# quadcopter.net
KiCad netlist of a schematic drawn in EAGLE
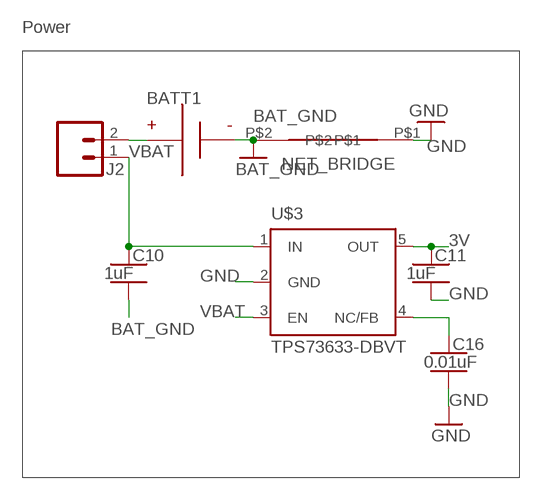
[diagram p0: schematic, sheet 1, part 1 of 2]
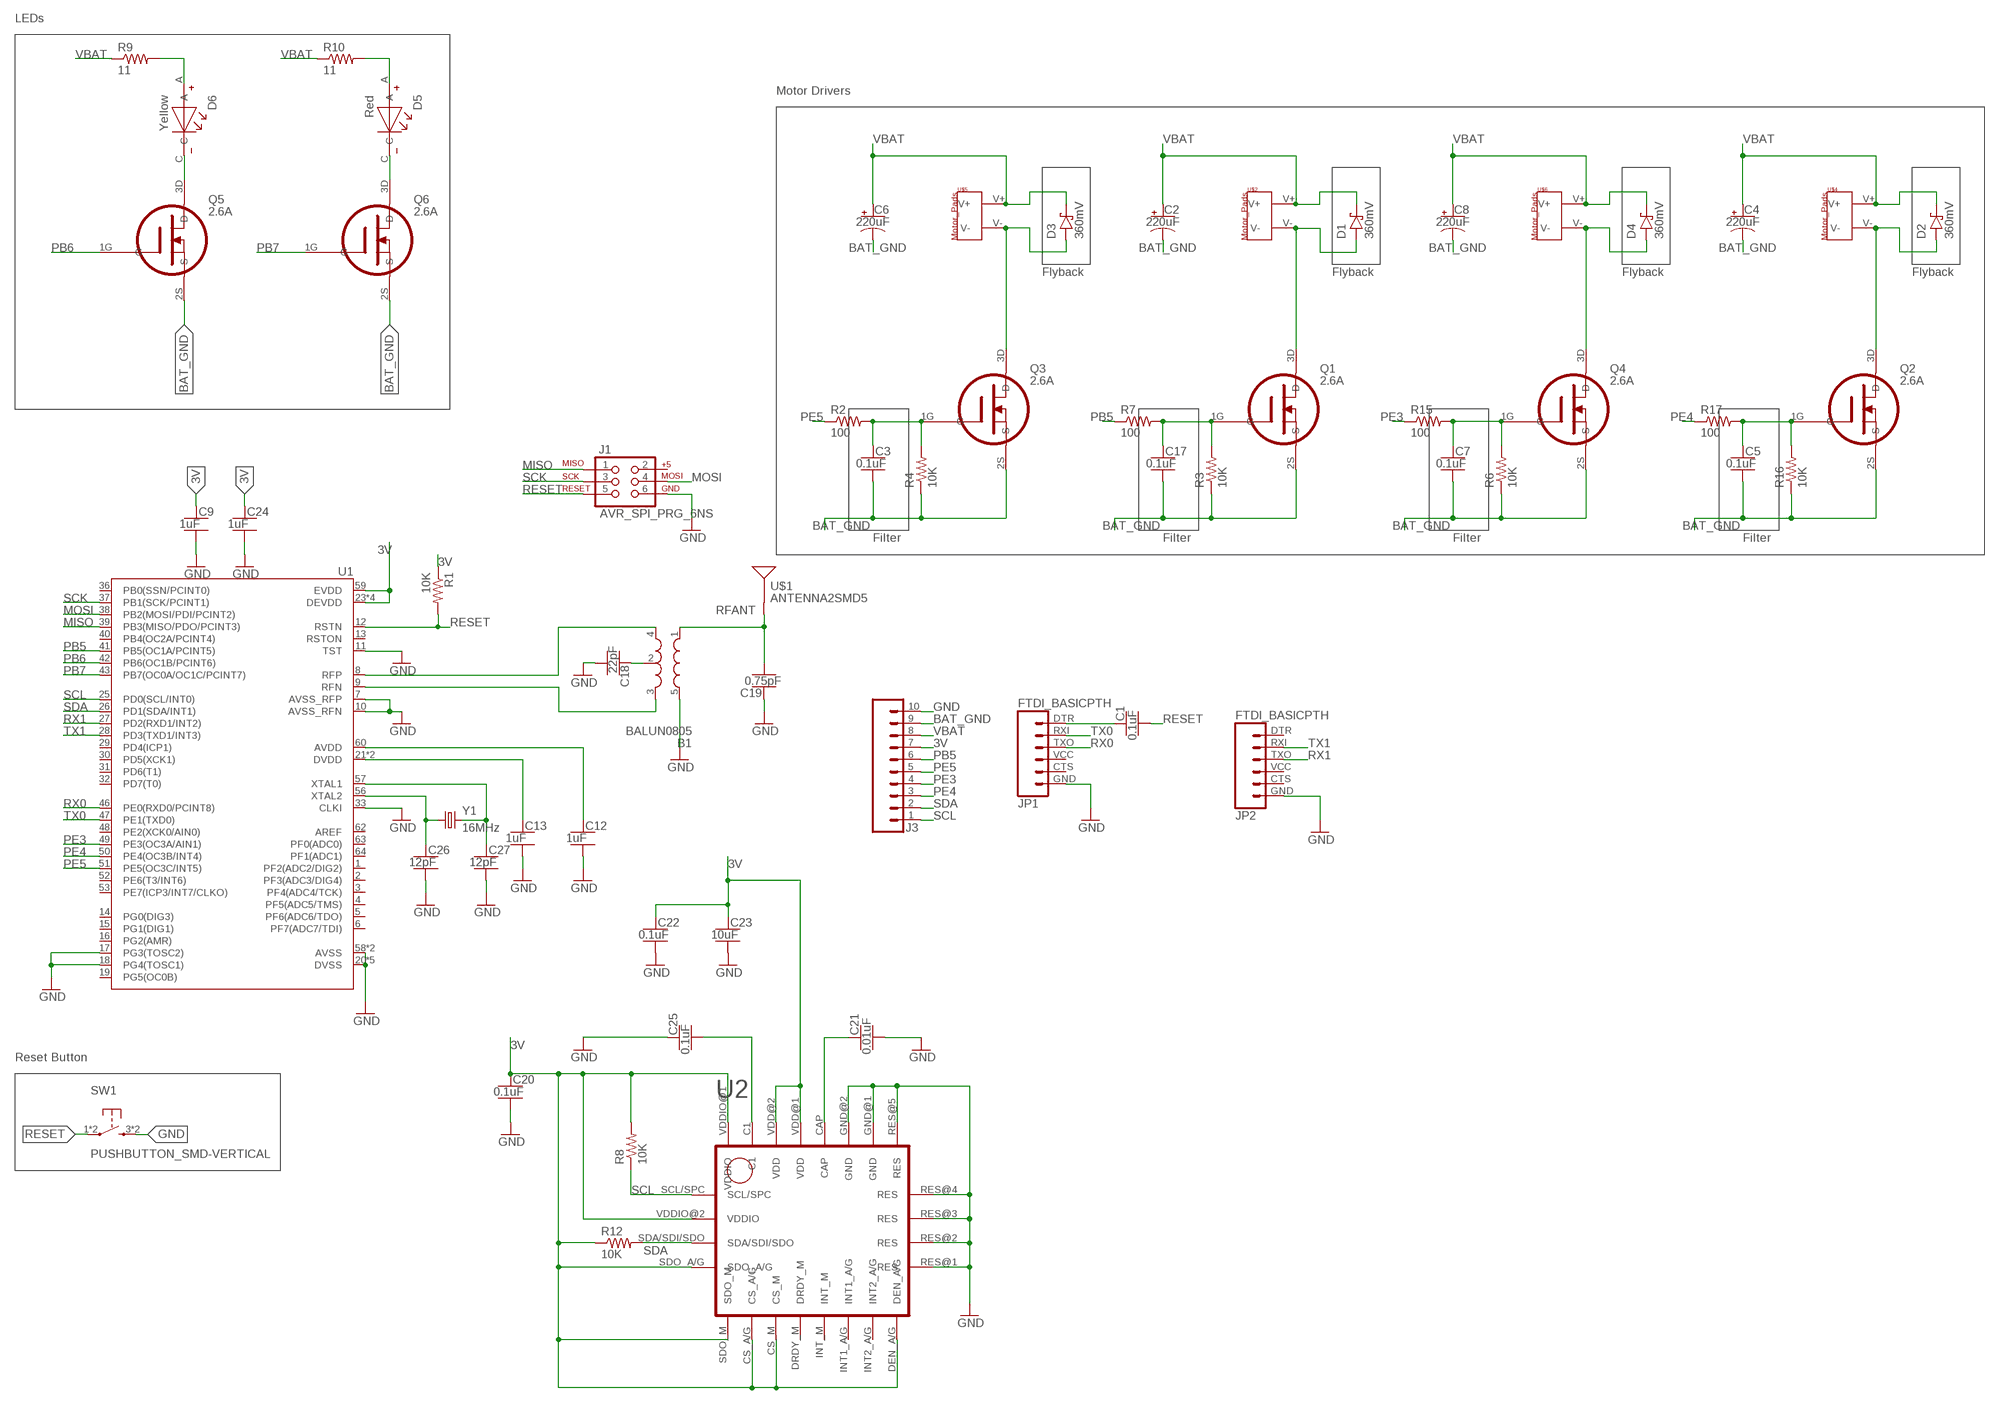
[diagram p1: schematic, sheet 1, part 2 of 2]

(export (version "E")
  (design (tool "Eeschema 10.0.6"))
  (components
    (comp (ref "B1")
      (value "BALUN0805")
      (footprint "eagle-import:BALUN")
      (fields (field (name "MFR") "Wurth Electronics Inc") (field (name "MPN") "748421245"))
      (libsource (lib "eagle-import") (part "BALUN0805"))
    )
    (comp (ref "BATT1")
      (value "BATTERY-HUBSAN-W/HOLDER")
      (footprint "eagle-import:BATTERY-W_HOLDER-380MAH-HUBSAN")
      (fields
        (field (name "MFR") "HUBSAN")
        (field (name "MPN") "X4-H107C-8-in-1")
        (field (name "CREATOR") "Swanson")
      )
      (libsource (lib "eagle-import") (part "BATTERY-HUBSAN-W/HOLDER"))
    )
    (comp (ref "C1")
      (value "0.1uF")
      (footprint "eagle-import:CERAMIC_CAP_0805")
      (fields
        (field (name "MFR") "Murata Electronics North America")
        (field (name "MPN") "GRM21BR71H104KA01L")
        (field (name "CREATOR") "SWANSON")
      )
      (libsource (lib "eagle-import") (part "CERAMIC_CAP-0805-0.1UF"))
    )
    (comp (ref "C2")
      (value "220uF")
      (footprint "eagle-import:CAPMP7343X310_HS")
      (fields (field (name "MFR") "AVX Corporation") (field (name "MPN") "TAJD227K006RNJ"))
      (libsource (lib "eagle-import") (part "CAPACITOR-POL_SMD-7043-D_TANTALUM-220UF"))
    )
    (comp (ref "C3")
      (value "0.1uF")
      (footprint "eagle-import:CAPC2012X140_HS")
      (fields
        (field (name "MFR") "Murata Electronics North America")
        (field (name "MPN") "GRM21BR71H104KA01L")
      )
      (libsource (lib "eagle-import") (part "CAPACITOR-NP_SMD-2012-0805_CERAMIC-0.1UF"))
    )
    (comp (ref "C4")
      (value "220uF")
      (footprint "eagle-import:CAPMP7343X310_HS")
      (fields (field (name "MFR") "AVX Corporation") (field (name "MPN") "TAJD227K006RNJ"))
      (libsource (lib "eagle-import") (part "CAPACITOR-POL_SMD-7043-D_TANTALUM-220UF"))
    )
    (comp (ref "C5")
      (value "0.1uF")
      (footprint "eagle-import:CAPC2012X140_HS")
      (fields
        (field (name "MFR") "Murata Electronics North America")
        (field (name "MPN") "GRM21BR71H104KA01L")
      )
      (libsource (lib "eagle-import") (part "CAPACITOR-NP_SMD-2012-0805_CERAMIC-0.1UF"))
    )
    (comp (ref "C6")
      (value "220uF")
      (footprint "eagle-import:CAPMP7343X310_HS")
      (fields (field (name "MFR") "AVX Corporation") (field (name "MPN") "TAJD227K006RNJ"))
      (libsource (lib "eagle-import") (part "CAPACITOR-POL_SMD-7043-D_TANTALUM-220UF"))
    )
    (comp (ref "C7")
      (value "0.1uF")
      (footprint "eagle-import:CAPC2012X140_HS")
      (fields
        (field (name "MFR") "Murata Electronics North America")
        (field (name "MPN") "GRM21BR71H104KA01L")
      )
      (libsource (lib "eagle-import") (part "CAPACITOR-NP_SMD-2012-0805_CERAMIC-0.1UF"))
    )
    (comp (ref "C8")
      (value "220uF")
      (footprint "eagle-import:CAPMP7343X310_HS")
      (fields (field (name "MFR") "AVX Corporation") (field (name "MPN") "TAJD227K006RNJ"))
      (libsource (lib "eagle-import") (part "CAPACITOR-POL_SMD-7043-D_TANTALUM-220UF"))
    )
    (comp (ref "C9")
      (value "1uF")
      (footprint "eagle-import:CAPC2012X140_HS")
      (fields
        (field (name "MFR") "Murata Electronics North America")
        (field (name "MPN") "GRM21BR71H105KA12L")
      )
      (libsource (lib "eagle-import") (part "CAPACITOR-NP_SMD-2012-0805_CERAMIC-1UF"))
    )
    (comp (ref "C10")
      (value "1uF")
      (footprint "eagle-import:CAPC2012X140_HS")
      (fields
        (field (name "MFR") "Murata Electronics North America")
        (field (name "MPN") "GRM21BR71H105KA12L")
      )
      (libsource (lib "eagle-import") (part "CAPACITOR-NP_SMD-2012-0805_CERAMIC-1UF"))
    )
    (comp (ref "C11")
      (value "1uF")
      (footprint "eagle-import:CAPC2012X140_HS")
      (fields
        (field (name "MFR") "Murata Electronics North America")
        (field (name "MPN") "GRM21BR71H105KA12L")
      )
      (libsource (lib "eagle-import") (part "CAPACITOR-NP_SMD-2012-0805_CERAMIC-1UF"))
    )
    (comp (ref "C12")
      (value "1uF")
      (footprint "eagle-import:CAPC2012X140_HS")
      (fields
        (field (name "MFR") "Murata Electronics North America")
        (field (name "MPN") "GRM21BR71H105KA12L")
      )
      (libsource (lib "eagle-import") (part "CAPACITOR-NP_SMD-2012-0805_CERAMIC-1UF"))
    )
    (comp (ref "C13")
      (value "1uF")
      (footprint "eagle-import:CAPC2012X140_HS")
      (fields
        (field (name "MFR") "Murata Electronics North America")
        (field (name "MPN") "GRM21BR71H105KA12L")
      )
      (libsource (lib "eagle-import") (part "CAPACITOR-NP_SMD-2012-0805_CERAMIC-1UF"))
    )
    (comp (ref "C16")
      (value "0.01uF")
      (footprint "eagle-import:CAPC2012X140_HS")
      (fields
        (field (name "MFR") "Murata Electronics North America")
        (field (name "MPN") "GRM2195C1H103FA01D")
      )
      (libsource (lib "eagle-import") (part "CAPACITOR-NP_SMD-2012-0805_CERAMIC-0.01UF"))
    )
    (comp (ref "C17")
      (value "0.1uF")
      (footprint "eagle-import:CAPC2012X140_HS")
      (fields
        (field (name "MFR") "Murata Electronics North America")
        (field (name "MPN") "GRM21BR71H104KA01L")
      )
      (libsource (lib "eagle-import") (part "CAPACITOR-NP_SMD-2012-0805_CERAMIC-0.1UF"))
    )
    (comp (ref "C18")
      (value "22pF")
      (footprint "eagle-import:CAPC2012X140_HS")
      (fields
        (field (name "MFR") "Murata Electronics North America")
        (field (name "MPN") "GRM21A5C2E220JW01D")
      )
      (libsource (lib "eagle-import") (part "CAPACITOR-NP_SMD-2012-0805_CERAMIC-22PF"))
    )
    (comp (ref "C19")
      (value "0.75pF")
      (footprint "eagle-import:CAPC2012X140_HS")
      (fields
        (field (name "MFR") "Murata Electronics North America")
        (field (name "MPN") "GQM2195C2AR75CB01D")
      )
      (libsource (lib "eagle-import") (part "CAPACITOR-NP_SMD-2012-0805_CERAMIC-0.75PF"))
    )
    (comp (ref "C20")
      (value "0.1uF")
      (footprint "eagle-import:CAPC2012X140_HS")
      (fields
        (field (name "MFR") "Murata Electronics North America")
        (field (name "MPN") "GRM21BR71H104KA01L")
      )
      (libsource (lib "eagle-import") (part "CAPACITOR-NP_SMD-2012-0805_CERAMIC-0.1UF"))
    )
    (comp (ref "C21")
      (value "0.01uF")
      (footprint "eagle-import:CAPC2012X140_HS")
      (fields
        (field (name "MFR") "Murata Electronics North America")
        (field (name "MPN") "GRM2195C1H103FA01D")
      )
      (libsource (lib "eagle-import") (part "CAPACITOR-NP_SMD-2012-0805_CERAMIC-0.01UF"))
    )
    (comp (ref "C22")
      (value "0.1uF")
      (footprint "eagle-import:CAPC2012X140_HS")
      (fields
        (field (name "MFR") "Murata Electronics North America")
        (field (name "MPN") "GRM21BR71H104KA01L")
      )
      (libsource (lib "eagle-import") (part "CAPACITOR-NP_SMD-2012-0805_CERAMIC-0.1UF"))
    )
    (comp (ref "C23")
      (value "10uF")
      (footprint "eagle-import:CAPC2012X140_HS")
      (fields
        (field (name "MFR") "Murata Electronics North America")
        (field (name "MPN") "GRM21BR61E106KA73L")
      )
      (libsource (lib "eagle-import") (part "CAPACITOR-NP_SMD-2012-0805_CERAMIC-10UF"))
    )
    (comp (ref "C24")
      (value "1uF")
      (footprint "eagle-import:CAPC2012X140_HS")
      (fields
        (field (name "MFR") "Murata Electronics North America")
        (field (name "MPN") "GRM21BR71H105KA12L")
      )
      (libsource (lib "eagle-import") (part "CAPACITOR-NP_SMD-2012-0805_CERAMIC-1UF"))
    )
    (comp (ref "C25")
      (value "0.1uF")
      (footprint "eagle-import:CAPC2012X140_HS")
      (fields
        (field (name "MFR") "Murata Electronics North America")
        (field (name "MPN") "GRM21BR71H104KA01L")
      )
      (libsource (lib "eagle-import") (part "CAPACITOR-NP_SMD-2012-0805_CERAMIC-0.1UF"))
    )
    (comp (ref "C26")
      (value "12pF")
      (footprint "eagle-import:CAPC2012X140_HS")
      (fields
        (field (name "MFR") "Murata Electronics North America")
        (field (name "MPN") "GRM21A5C2E120JW01D")
      )
      (libsource (lib "eagle-import") (part "CAPACITOR-NP_SMD-2012-0805_CERAMIC-12PF"))
    )
    (comp (ref "C27")
      (value "12pF")
      (footprint "eagle-import:CAPC2012X140_HS")
      (fields
        (field (name "MFR") "Murata Electronics North America")
        (field (name "MPN") "GRM21A5C2E120JW01D")
      )
      (libsource (lib "eagle-import") (part "CAPACITOR-NP_SMD-2012-0805_CERAMIC-12PF"))
    )
    (comp (ref "D1")
      (value "360mV")
      (footprint "eagle-import:SOD3716X135_HS")
      (fields
        (field (name "MFR") "Toshiba Semiconductor and Storage")
        (field (name "MPN") "CRS08(TE85L,Q,M)")
      )
      (libsource (lib "eagle-import") (part "DIODE-SCHOTTKY_SMD-SOD123-360MV"))
    )
    (comp (ref "D2")
      (value "360mV")
      (footprint "eagle-import:SOD3716X135_HS")
      (fields
        (field (name "MFR") "Toshiba Semiconductor and Storage")
        (field (name "MPN") "CRS08(TE85L,Q,M)")
      )
      (libsource (lib "eagle-import") (part "DIODE-SCHOTTKY_SMD-SOD123-360MV"))
    )
    (comp (ref "D3")
      (value "360mV")
      (footprint "eagle-import:SOD3716X135_HS")
      (fields
        (field (name "MFR") "Toshiba Semiconductor and Storage")
        (field (name "MPN") "CRS08(TE85L,Q,M)")
      )
      (libsource (lib "eagle-import") (part "DIODE-SCHOTTKY_SMD-SOD123-360MV"))
    )
    (comp (ref "D4")
      (value "360mV")
      (footprint "eagle-import:SOD3716X135_HS")
      (fields
        (field (name "MFR") "Toshiba Semiconductor and Storage")
        (field (name "MPN") "CRS08(TE85L,Q,M)")
      )
      (libsource (lib "eagle-import") (part "DIODE-SCHOTTKY_SMD-SOD123-360MV"))
    )
    (comp (ref "D5")
      (value "Red")
      (footprint "eagle-import:LED_VLMX51Z1AA")
      (fields
        (field (name "MFR") "Vishay")
        (field (name "MPN") "VLMR51Z1AA-GS08")
        (field (name "CREATOR") "Jason Shiuan")
      )
      (libsource (lib "eagle-import") (part "LED_VLMX51Z1AARED"))
    )
    (comp (ref "D6")
      (value "Yellow")
      (footprint "eagle-import:LED_VLMX51Z1AA")
      (fields
        (field (name "MFR") "Vishay")
        (field (name "MPN") "VLMY51Z1AA-GS08")
        (field (name "CREATOR") "Jason Shiuan")
      )
      (libsource (lib "eagle-import") (part "LED_VLMX51Z1AAYELLOW"))
    )
    (comp (ref "J1")
      (value "AVR_SPI_PRG_6NS")
      (footprint "eagle-import:2X3-NS")
      (fields (field (name "MFR") "Amphenol FCI") (field (name "MPN") "67997-206HLF"))
      (libsource (lib "eagle-import") (part "AVR_SPI_PRG_6NS"))
    )
    (comp (ref "J2")
      (value "MALE_HEADER_2POS-2X1-0.1IN")
      (footprint "eagle-import:MALE_HEADER_2X1_0.1IN")
      (fields
        (field (name "MFR") "3M")
        (field (name "MPN") "961102-6404-AR")
        (field (name "CREATOR") "SWANSON")
      )
      (libsource (lib "eagle-import") (part "MALE_HEADER_2POS-2X1-0.1IN"))
    )
    (comp (ref "J3")
      (value "SIP-10_TH-254X10")
      (footprint "eagle-import:HDRV10W63P254_10X1_2540X254H838_HS")
      (fields (field (name "MFR") "Amphenol FCI") (field (name "MPN") "68000-110HLF"))
      (libsource (lib "eagle-import") (part "SIP-10_TH-254X10"))
    )
    (comp (ref "JP1")
      (value "FTDI_BASICPTH")
      (footprint "eagle-import:FTDI_BASIC")
      (fields (field (name "MFR") "Amphenol FCI") (field (name "MPN") "68016-406HLF"))
      (libsource (lib "eagle-import") (part "FTDI_BASICPTH"))
    )
    (comp (ref "JP2")
      (value "FTDI_BASICPTH")
      (footprint "eagle-import:FTDI_BASIC")
      (fields (field (name "MFR") "Amphenol FCI") (field (name "MPN") "68016-406HLF"))
      (libsource (lib "eagle-import") (part "FTDI_BASICPTH"))
    )
    (comp (ref "NET_BRIDGE")
      (value "NET_BRIDGE")
      (footprint "eagle-import:NET_BRIDGE")
      (fields (field (name "CREATPR") "Jason Shiuan"))
      (libsource (lib "eagle-import") (part "NET_BRIDGE"))
    )
    (comp (ref "Q1")
      (value "2.6A")
      (footprint "eagle-import:N_MOSFET_SI2302CDS_T1_E3")
      (fields
        (field (name "MFR") "Vishay Siliconix")
        (field (name "MPN") "SI2302CDS-T1-E3")
        (field (name "CREATOR") "Connie Du")
      )
      (libsource (lib "eagle-import") (part "N_MOSFET_SI2302CDS_T1_E3"))
    )
    (comp (ref "Q2")
      (value "2.6A")
      (footprint "eagle-import:N_MOSFET_SI2302CDS_T1_E3")
      (fields
        (field (name "MFR") "Vishay Siliconix")
        (field (name "MPN") "SI2302CDS-T1-E3")
        (field (name "CREATOR") "Connie Du")
      )
      (libsource (lib "eagle-import") (part "N_MOSFET_SI2302CDS_T1_E3"))
    )
    (comp (ref "Q3")
      (value "2.6A")
      (footprint "eagle-import:N_MOSFET_SI2302CDS_T1_E3")
      (fields
        (field (name "MFR") "Vishay Siliconix")
        (field (name "MPN") "SI2302CDS-T1-E3")
        (field (name "CREATOR") "Connie Du")
      )
      (libsource (lib "eagle-import") (part "N_MOSFET_SI2302CDS_T1_E3"))
    )
    (comp (ref "Q4")
      (value "2.6A")
      (footprint "eagle-import:N_MOSFET_SI2302CDS_T1_E3")
      (fields
        (field (name "MFR") "Vishay Siliconix")
        (field (name "MPN") "SI2302CDS-T1-E3")
        (field (name "CREATOR") "Connie Du")
      )
      (libsource (lib "eagle-import") (part "N_MOSFET_SI2302CDS_T1_E3"))
    )
    (comp (ref "Q5")
      (value "2.6A")
      (footprint "eagle-import:N_MOSFET_SI2302CDS_T1_E3")
      (fields
        (field (name "MFR") "Vishay Siliconix")
        (field (name "MPN") "SI2302CDS-T1-E3")
        (field (name "CREATOR") "Connie Du")
      )
      (libsource (lib "eagle-import") (part "N_MOSFET_SI2302CDS_T1_E3"))
    )
    (comp (ref "Q6")
      (value "2.6A")
      (footprint "eagle-import:N_MOSFET_SI2302CDS_T1_E3")
      (fields
        (field (name "MFR") "Vishay Siliconix")
        (field (name "MPN") "SI2302CDS-T1-E3")
        (field (name "CREATOR") "Connie Du")
      )
      (libsource (lib "eagle-import") (part "N_MOSFET_SI2302CDS_T1_E3"))
    )
    (comp (ref "R1")
      (value "10K")
      (footprint "eagle-import:RESC2012X60_HS")
      (fields (field (name "MFR") "Yageo") (field (name "MPN") "RC0805JR-0710KL"))
      (libsource (lib "eagle-import") (part "RESISTOR_SMD-2012-0805-10K"))
    )
    (comp (ref "R2")
      (value "100")
      (footprint "eagle-import:RESC2012X60_HS")
      (fields (field (name "MFR") "Yageo") (field (name "MPN") "RC0805JR-07100RL"))
      (libsource (lib "eagle-import") (part "RESISTOR_SMD-2012-0805-100"))
    )
    (comp (ref "R3")
      (value "10K")
      (footprint "eagle-import:RESC2012X60_HS")
      (fields (field (name "MFR") "Yageo") (field (name "MPN") "RC0805JR-0710KL"))
      (libsource (lib "eagle-import") (part "RESISTOR_SMD-2012-0805-10K"))
    )
    (comp (ref "R4")
      (value "10K")
      (footprint "eagle-import:RESC2012X60_HS")
      (fields (field (name "MFR") "Yageo") (field (name "MPN") "RC0805JR-0710KL"))
      (libsource (lib "eagle-import") (part "RESISTOR_SMD-2012-0805-10K"))
    )
    (comp (ref "R6")
      (value "10K")
      (footprint "eagle-import:RESC2012X60_HS")
      (fields (field (name "MFR") "Yageo") (field (name "MPN") "RC0805JR-0710KL"))
      (libsource (lib "eagle-import") (part "RESISTOR_SMD-2012-0805-10K"))
    )
    (comp (ref "R7")
      (value "100")
      (footprint "eagle-import:RESC2012X60_HS")
      (fields (field (name "MFR") "Yageo") (field (name "MPN") "RC0805JR-07100RL"))
      (libsource (lib "eagle-import") (part "RESISTOR_SMD-2012-0805-100"))
    )
    (comp (ref "R8")
      (value "10K")
      (footprint "eagle-import:RESC2012X60_HS")
      (fields (field (name "MFR") "Yageo") (field (name "MPN") "RC0805JR-0710KL"))
      (libsource (lib "eagle-import") (part "RESISTOR_SMD-2012-0805-10K"))
    )
    (comp (ref "R9")
      (value "11")
      (footprint "eagle-import:RESC2012X60_HS")
      (fields (field (name "MFR") "Yageo") (field (name "MPN") "RC1206FR-0711RL"))
      (libsource (lib "eagle-import") (part "RESISTOR_SMD-2012-0805-11"))
    )
    (comp (ref "R10")
      (value "11")
      (footprint "eagle-import:RESC2012X60_HS")
      (fields (field (name "MFR") "Yageo") (field (name "MPN") "RC1206FR-0711RL"))
      (libsource (lib "eagle-import") (part "RESISTOR_SMD-2012-0805-11"))
    )
    (comp (ref "R12")
      (value "10K")
      (footprint "eagle-import:RESC2012X60_HS")
      (fields (field (name "MFR") "Yageo") (field (name "MPN") "RC0805JR-0710KL"))
      (libsource (lib "eagle-import") (part "RESISTOR_SMD-2012-0805-10K"))
    )
    (comp (ref "R15")
      (value "100")
      (footprint "eagle-import:RESC2012X60_HS")
      (fields (field (name "MFR") "Yageo") (field (name "MPN") "RC0805JR-07100RL"))
      (libsource (lib "eagle-import") (part "RESISTOR_SMD-2012-0805-100"))
    )
    (comp (ref "R16")
      (value "10K")
      (footprint "eagle-import:RESC2012X60_HS")
      (fields (field (name "MFR") "Yageo") (field (name "MPN") "RC0805JR-0710KL"))
      (libsource (lib "eagle-import") (part "RESISTOR_SMD-2012-0805-10K"))
    )
    (comp (ref "R17")
      (value "100")
      (footprint "eagle-import:RESC2012X60_HS")
      (fields (field (name "MFR") "Yageo") (field (name "MPN") "RC0805JR-07100RL"))
      (libsource (lib "eagle-import") (part "RESISTOR_SMD-2012-0805-100"))
    )
    (comp (ref "SW1")
      (value "PUSHBUTTON_SMD-VERTICAL")
      (footprint "eagle-import:TE_FSM8JSMA_HS")
      (libsource (lib "eagle-import") (part "PUSHBUTTON_SMD-VERTICAL"))
    )
    (comp (ref "U$1")
      (value "ANTENNA2SMD5")
      (footprint "eagle-import:ANTENNA-CHIP5")
      (fields (field (name "MFR") "Linx Technologies Inc.") (field (name "MPN") "ANT-2.45-CHP-T"))
      (libsource (lib "eagle-import") (part "ANTENNA2SMD5"))
    )
    (comp (ref "U$2")
      (value "MOTOR_PADS")
      (footprint "eagle-import:MOTOR_PADS")
      (fields (field (name "MFR") "NA"))
      (libsource (lib "eagle-import") (part "MOTOR_PADS"))
    )
    (comp (ref "U$3")
      (value "TPS73633-DBVT")
      (footprint "eagle-import:SOT23-DBV")
      (fields (field (name "MFR") "Texas Instruments") (field (name "MPN") "LP3985IM5X-3.0/NOPB"))
      (libsource (lib "eagle-import") (part "TPS73633-DBVT"))
    )
    (comp (ref "U$4")
      (value "MOTOR_PADS")
      (footprint "eagle-import:MOTOR_PADS")
      (fields (field (name "MFR") "NA"))
      (libsource (lib "eagle-import") (part "MOTOR_PADS"))
    )
    (comp (ref "U$5")
      (value "MOTOR_PADS")
      (footprint "eagle-import:MOTOR_PADS")
      (fields (field (name "MFR") "NA"))
      (libsource (lib "eagle-import") (part "MOTOR_PADS"))
    )
    (comp (ref "U$6")
      (value "MOTOR_PADS")
      (footprint "eagle-import:MOTOR_PADS")
      (fields (field (name "MFR") "NA"))
      (libsource (lib "eagle-import") (part "MOTOR_PADS"))
    )
    (comp (ref "U1")
      (value "ATMEGA128RFA1")
      (footprint "eagle-import:QFN-64")
      (fields
        (field (name "MFR") "Atmel")
        (field (name "MPN") "ATMEGA128RFA1-ZUR00")
        (field (name "CREATOR") "Swanson")
      )
      (libsource (lib "eagle-import") (part "ATMEGA128RFA1"))
    )
    (comp (ref "U2")
      (value "IMU_LSM9DS1TR")
      (footprint "eagle-import:IMU_LSM9DS1TR")
      (fields
        (field (name "MFR") "STMicroelectronics")
        (field (name "MPN") "LSM9DS1TR")
        (field (name "CREATOR") "Connie Du")
      )
      (libsource (lib "eagle-import") (part "IMU_LSM9DS1TR"))
    )
    (comp (ref "Y1")
      (value "16MHz")
      (footprint "eagle-import:CRYSTAL-SMD-5X3")
      (fields (field (name "MFR") "Abracon LLC") (field (name "MPN") "ABM3B-16.000MHZ-B2-T"))
      (libsource (lib "eagle-import") (part "CRYSTAL5X3"))
    )
  )
  (nets
    (net (code "1") (name "/MISO") (class "Default")
      (node (ref "J1") (pin "1") (pinfunction "1_1") (pintype "passive"))
      (node (ref "U1") (pin "39") (pinfunction "PB3(MISO/PDO/PCINT3)_39") (pintype "bidirectional"))
    )
    (net (code "2") (name "/MOSI") (class "Default")
      (node (ref "J1") (pin "4") (pinfunction "4_4") (pintype "passive"))
      (node (ref "U1") (pin "38") (pinfunction "PB2(MOSI/PDI/PCINT2)_38") (pintype "bidirectional"))
    )
    (net (code "3") (name "/PB5") (class "Default")
      (node (ref "J3") (pin "6") (pinfunction "6_6") (pintype "passive"))
      (node (ref "R7") (pin "1") (pinfunction "1_1") (pintype "passive"))
      (node (ref "U1") (pin "41") (pinfunction "PB5(OC1A/PCINT5)_41") (pintype "bidirectional"))
    )
    (net (code "4") (name "/PB6") (class "Default")
      (node (ref "Q5") (pin "1G") (pinfunction "G_1G") (pintype "bidirectional"))
      (node (ref "U1") (pin "42") (pinfunction "PB6(OC1B/PCINT6)_42") (pintype "bidirectional"))
    )
    (net (code "5") (name "/PB7") (class "Default")
      (node (ref "Q6") (pin "1G") (pinfunction "G_1G") (pintype "bidirectional"))
      (node (ref "U1") (pin "43") (pinfunction "PB7(OC0A/OC1C/PCINT7)_43") (pintype "bidirectional"))
    )
    (net (code "6") (name "/PE3") (class "Default")
      (node (ref "J3") (pin "4") (pinfunction "4_4") (pintype "passive"))
      (node (ref "R15") (pin "1") (pinfunction "1_1") (pintype "passive"))
      (node (ref "U1") (pin "49") (pinfunction "PE3(OC3A/AIN1)_49") (pintype "bidirectional"))
    )
    (net (code "7") (name "/PE4") (class "Default")
      (node (ref "J3") (pin "3") (pinfunction "3_3") (pintype "passive"))
      (node (ref "R17") (pin "1") (pinfunction "1_1") (pintype "passive"))
      (node (ref "U1") (pin "50") (pinfunction "PE4(OC3B/INT4)_50") (pintype "bidirectional"))
    )
    (net (code "8") (name "/PE5") (class "Default")
      (node (ref "J3") (pin "5") (pinfunction "5_5") (pintype "passive"))
      (node (ref "R2") (pin "1") (pinfunction "1_1") (pintype "passive"))
      (node (ref "U1") (pin "51") (pinfunction "PE5(OC3C/INT5)_51") (pintype "bidirectional"))
    )
    (net (code "9") (name "/RFANT") (class "Default")
      (node (ref "B1") (pin "1") (pinfunction "IN_1") (pintype "bidirectional"))
      (node (ref "C19") (pin "2") (pinfunction "2_2") (pintype "passive"))
      (node (ref "U$1") (pin "FEED") (pinfunction "SIGNAL_FEED") (pintype "bidirectional"))
    )
    (net (code "10") (name "/RX0") (class "Default")
      (node (ref "JP1") (pin "TXO") (pinfunction "3_TXO") (pintype "passive"))
      (node (ref "U1") (pin "46") (pinfunction "PE0(RXD0/PCINT8)_46") (pintype "bidirectional"))
    )
    (net (code "11") (name "/RX1") (class "Default")
      (node (ref "JP2") (pin "TXO") (pinfunction "3_TXO") (pintype "passive"))
      (node (ref "U1") (pin "27") (pinfunction "PD2(RXD1/INT2)_27") (pintype "bidirectional"))
    )
    (net (code "12") (name "/SCK") (class "Default")
      (node (ref "J1") (pin "3") (pinfunction "3_3") (pintype "passive"))
      (node (ref "U1") (pin "37") (pinfunction "PB1(SCK/PCINT1)_37") (pintype "bidirectional"))
    )
    (net (code "13") (name "/SCL") (class "Default")
      (node (ref "J3") (pin "1") (pinfunction "1_1") (pintype "passive"))
      (node (ref "R8") (pin "1") (pinfunction "1_1") (pintype "passive"))
      (node (ref "U1") (pin "25") (pinfunction "PD0(SCL/INT0)_25") (pintype "bidirectional"))
      (node (ref "U2") (pin "SCL/SPC") (pinfunction "SCL/SPC_SCL/SPC") (pintype "bidirectional"))
    )
    (net (code "14") (name "/SDA") (class "Default")
      (node (ref "J3") (pin "2") (pinfunction "2_2") (pintype "passive"))
      (node (ref "R12") (pin "2") (pinfunction "2_2") (pintype "passive"))
      (node (ref "U1") (pin "26") (pinfunction "PD1(SDA/INT1)_26") (pintype "bidirectional"))
      (node (ref "U2") (pin "SDA/SDI/SDO") (pinfunction "SDA/SDI/SDO_SDA/SDI/SDO") (pintype "bidirectional"))
    )
    (net (code "15") (name "/TX0") (class "Default")
      (node (ref "JP1") (pin "RXI") (pinfunction "2_RXI") (pintype "passive"))
      (node (ref "U1") (pin "47") (pinfunction "PE1(TXD0)_47") (pintype "bidirectional"))
    )
    (net (code "16") (name "/TX1") (class "Default")
      (node (ref "JP2") (pin "RXI") (pinfunction "2_RXI") (pintype "passive"))
      (node (ref "U1") (pin "28") (pinfunction "PD3(TXD1/INT3)_28") (pintype "bidirectional"))
    )
    (net (code "17") (name "/VBAT") (class "Default")
      (node (ref "C10") (pin "1") (pinfunction "1_1") (pintype "passive"))
      (node (ref "C2") (pin "1") (pinfunction "+_1") (pintype "passive"))
      (node (ref "C4") (pin "1") (pinfunction "+_1") (pintype "passive"))
      (node (ref "C6") (pin "1") (pinfunction "+_1") (pintype "passive"))
      (node (ref "C8") (pin "1") (pinfunction "+_1") (pintype "passive"))
      (node (ref "D1") (pin "C") (pinfunction "C_C") (pintype "passive"))
      (node (ref "D2") (pin "C") (pinfunction "C_C") (pintype "passive"))
      (node (ref "D3") (pin "C") (pinfunction "C_C") (pintype "passive"))
      (node (ref "D4") (pin "C") (pinfunction "C_C") (pintype "passive"))
      (node (ref "J2") (pin "1") (pinfunction "1_1") (pintype "passive"))
      (node (ref "J3") (pin "8") (pinfunction "8_8") (pintype "passive"))
      (node (ref "R10") (pin "1") (pinfunction "1_1") (pintype "passive"))
      (node (ref "R9") (pin "1") (pinfunction "1_1") (pintype "passive"))
      (node (ref "U$2") (pin "V+") (pinfunction "V+_V+") (pintype "bidirectional"))
      (node (ref "U$3") (pin "1") (pinfunction "IN_1") (pintype "input"))
      (node (ref "U$3") (pin "3") (pinfunction "EN_3") (pintype "input"))
      (node (ref "U$4") (pin "V+") (pinfunction "V+_V+") (pintype "bidirectional"))
      (node (ref "U$5") (pin "V+") (pinfunction "V+_V+") (pintype "bidirectional"))
      (node (ref "U$6") (pin "V+") (pinfunction "V+_V+") (pintype "bidirectional"))
    )
    (net (code "18") (name "3V") (class "Default")
      (node (ref "C11") (pin "1") (pinfunction "1_1") (pintype "passive"))
      (node (ref "C20") (pin "1") (pinfunction "1_1") (pintype "passive"))
      (node (ref "C22") (pin "1") (pinfunction "1_1") (pintype "passive"))
      (node (ref "C23") (pin "1") (pinfunction "1_1") (pintype "passive"))
      (node (ref "C24") (pin "1") (pinfunction "1_1") (pintype "passive"))
      (node (ref "C9") (pin "1") (pinfunction "1_1") (pintype "passive"))
      (node (ref "J3") (pin "7") (pinfunction "7_7") (pintype "passive"))
      (node (ref "R1") (pin "1") (pinfunction "1_1") (pintype "passive"))
      (node (ref "R12") (pin "1") (pinfunction "1_1") (pintype "passive"))
      (node (ref "R8") (pin "2") (pinfunction "2_2") (pintype "passive"))
      (node (ref "U$3") (pin "5") (pinfunction "OUT_5") (pintype "passive"))
      (node (ref "U1") (pin "23") (pinfunction "DEVDD_23") (pintype "bidirectional"))
      (node (ref "U1") (pin "34") (pinfunction "DEVDD_34") (pintype "bidirectional"))
      (node (ref "U1") (pin "44") (pinfunction "DEVDD_44") (pintype "bidirectional"))
      (node (ref "U1") (pin "54") (pinfunction "DEVDD_54") (pintype "bidirectional"))
      (node (ref "U1") (pin "59") (pinfunction "EVDD_59") (pintype "bidirectional"))
      (node (ref "U2") (pin "CS_A/G") (pinfunction "CS_A/G_CS_A/G") (pintype "bidirectional"))
      (node (ref "U2") (pin "CS_M") (pinfunction "CS_M_CS_M") (pintype "bidirectional"))
      (node (ref "U2") (pin "DEN_A/G") (pinfunction "DEN_A/G_DEN_A/G") (pintype "bidirectional"))
      (node (ref "U2") (pin "SDO_A/G") (pinfunction "SDO_A/G_SDO_A/G") (pintype "bidirectional"))
      (node (ref "U2") (pin "SDO_M") (pinfunction "SDO_M_SDO_M") (pintype "bidirectional"))
      (node (ref "U2") (pin "VDD@1") (pinfunction "VDD_VDD@1") (pintype "bidirectional"))
      (node (ref "U2") (pin "VDD@2") (pinfunction "VDD_VDD@2") (pintype "bidirectional"))
      (node (ref "U2") (pin "VDDIO@1") (pinfunction "VDDIO_VDDIO@1") (pintype "bidirectional"))
      (node (ref "U2") (pin "VDDIO@2") (pinfunction "VDDIO_VDDIO@2") (pintype "bidirectional"))
    )
    (net (code "19") (name "BAT_GND") (class "Default")
      (node (ref "BATT1") (pin "-") (pinfunction "N_-") (pintype "bidirectional"))
      (node (ref "C10") (pin "2") (pinfunction "2_2") (pintype "passive"))
      (node (ref "C17") (pin "2") (pinfunction "2_2") (pintype "passive"))
      (node (ref "C2") (pin "2") (pinfunction "-_2") (pintype "passive"))
      (node (ref "C3") (pin "2") (pinfunction "2_2") (pintype "passive"))
      (node (ref "C4") (pin "2") (pinfunction "-_2") (pintype "passive"))
      (node (ref "C5") (pin "2") (pinfunction "2_2") (pintype "passive"))
      (node (ref "C6") (pin "2") (pinfunction "-_2") (pintype "passive"))
      (node (ref "C7") (pin "2") (pinfunction "2_2") (pintype "passive"))
      (node (ref "C8") (pin "2") (pinfunction "-_2") (pintype "passive"))
      (node (ref "J3") (pin "9") (pinfunction "9_9") (pintype "passive"))
      (node (ref "NET_BRIDGE") (pin "P$2") (pinfunction "P$2_P$2") (pintype "bidirectional"))
      (node (ref "Q1") (pin "2S") (pinfunction "S_2S") (pintype "bidirectional"))
      (node (ref "Q2") (pin "2S") (pinfunction "S_2S") (pintype "bidirectional"))
      (node (ref "Q3") (pin "2S") (pinfunction "S_2S") (pintype "bidirectional"))
      (node (ref "Q4") (pin "2S") (pinfunction "S_2S") (pintype "bidirectional"))
      (node (ref "Q5") (pin "2S") (pinfunction "S_2S") (pintype "bidirectional"))
      (node (ref "Q6") (pin "2S") (pinfunction "S_2S") (pintype "bidirectional"))
      (node (ref "R16") (pin "1") (pinfunction "1_1") (pintype "passive"))
      (node (ref "R3") (pin "1") (pinfunction "1_1") (pintype "passive"))
      (node (ref "R4") (pin "1") (pinfunction "1_1") (pintype "passive"))
      (node (ref "R6") (pin "1") (pinfunction "1_1") (pintype "passive"))
    )
    (net (code "20") (name "GND") (class "Default")
      (node (ref "B1") (pin "5") (pinfunction "GND_5") (pintype "bidirectional"))
      (node (ref "C11") (pin "2") (pinfunction "2_2") (pintype "passive"))
      (node (ref "C12") (pin "2") (pinfunction "2_2") (pintype "passive"))
      (node (ref "C13") (pin "2") (pinfunction "2_2") (pintype "passive"))
      (node (ref "C16") (pin "2") (pinfunction "2_2") (pintype "passive"))
      (node (ref "C18") (pin "2") (pinfunction "2_2") (pintype "passive"))
      (node (ref "C19") (pin "1") (pinfunction "1_1") (pintype "passive"))
      (node (ref "C20") (pin "2") (pinfunction "2_2") (pintype "passive"))
      (node (ref "C21") (pin "2") (pinfunction "2_2") (pintype "passive"))
      (node (ref "C22") (pin "2") (pinfunction "2_2") (pintype "passive"))
      (node (ref "C23") (pin "2") (pinfunction "2_2") (pintype "passive"))
      (node (ref "C24") (pin "2") (pinfunction "2_2") (pintype "passive"))
      (node (ref "C25") (pin "1") (pinfunction "1_1") (pintype "passive"))
      (node (ref "C26") (pin "2") (pinfunction "2_2") (pintype "passive"))
      (node (ref "C27") (pin "2") (pinfunction "2_2") (pintype "passive"))
      (node (ref "C9") (pin "2") (pinfunction "2_2") (pintype "passive"))
      (node (ref "J1") (pin "6") (pinfunction "6_6") (pintype "passive"))
      (node (ref "J3") (pin "10") (pinfunction "10_10") (pintype "passive"))
      (node (ref "JP1") (pin "GND") (pinfunction "6_GND") (pintype "passive"))
      (node (ref "JP2") (pin "GND") (pinfunction "6_GND") (pintype "passive"))
      (node (ref "NET_BRIDGE") (pin "P$1") (pinfunction "P$1_P$1") (pintype "bidirectional"))
      (node (ref "SW1") (pin "3") (pinfunction "2_3") (pintype "passive"))
      (node (ref "SW1") (pin "4") (pinfunction "2_4") (pintype "passive"))
      (node (ref "U$3") (pin "2") (pinfunction "GND_2") (pintype "input"))
      (node (ref "U1") (pin "10") (pinfunction "AVSS_RFN_10") (pintype "bidirectional"))
      (node (ref "U1") (pin "11") (pinfunction "TST_11") (pintype "bidirectional"))
      (node (ref "U1") (pin "17") (pinfunction "PG3(TOSC2)_17") (pintype "bidirectional"))
      (node (ref "U1") (pin "18") (pinfunction "PG4(TOSC1)_18") (pintype "bidirectional"))
      (node (ref "U1") (pin "20") (pinfunction "DVSS_20") (pintype "bidirectional"))
      (node (ref "U1") (pin "24") (pinfunction "DVSS_24") (pintype "bidirectional"))
      (node (ref "U1") (pin "33") (pinfunction "CLKI_33") (pintype "bidirectional"))
      (node (ref "U1") (pin "35") (pinfunction "DVSS_35") (pintype "bidirectional"))
      (node (ref "U1") (pin "45") (pinfunction "DVSS_45") (pintype "bidirectional"))
      (node (ref "U1") (pin "55") (pinfunction "DVSS_55") (pintype "bidirectional"))
      (node (ref "U1") (pin "58") (pinfunction "AVSS_58") (pintype "bidirectional"))
      (node (ref "U1") (pin "61") (pinfunction "AVSS_61") (pintype "bidirectional"))
      (node (ref "U1") (pin "7") (pinfunction "AVSS_RFP_7") (pintype "bidirectional"))
      (node (ref "U2") (pin "GND@1") (pinfunction "GND_GND@1") (pintype "bidirectional"))
      (node (ref "U2") (pin "GND@2") (pinfunction "GND_GND@2") (pintype "bidirectional"))
      (node (ref "U2") (pin "RES@1") (pinfunction "RES_RES@1") (pintype "bidirectional"))
      (node (ref "U2") (pin "RES@2") (pinfunction "RES_RES@2") (pintype "bidirectional"))
      (node (ref "U2") (pin "RES@3") (pinfunction "RES_RES@3") (pintype "bidirectional"))
      (node (ref "U2") (pin "RES@4") (pinfunction "RES_RES@4") (pintype "bidirectional"))
      (node (ref "U2") (pin "RES@5") (pinfunction "RES_RES@5") (pintype "bidirectional"))
    )
    (net (code "21") (name "Net-(B1-GND-Pad2)") (class "Default")
      (node (ref "B1") (pin "2") (pinfunction "GND_2") (pintype "bidirectional"))
      (node (ref "C18") (pin "1") (pinfunction "1_1") (pintype "passive"))
    )
    (net (code "22") (name "Net-(B1-OUT1)") (class "Default")
      (node (ref "B1") (pin "4") (pinfunction "OUT1_4") (pintype "bidirectional"))
      (node (ref "U1") (pin "8") (pinfunction "RFP_8") (pintype "bidirectional"))
    )
    (net (code "23") (name "Net-(B1-OUT2)") (class "Default")
      (node (ref "B1") (pin "3") (pinfunction "OUT2_3") (pintype "bidirectional"))
      (node (ref "U1") (pin "9") (pinfunction "RFN_9") (pintype "bidirectional"))
    )
    (net (code "24") (name "Net-(BATT1-P)") (class "Default")
      (node (ref "BATT1") (pin "+") (pinfunction "P_+") (pintype "bidirectional"))
      (node (ref "J2") (pin "2") (pinfunction "2_2") (pintype "passive"))
    )
    (net (code "25") (name "Net-(C13-Pad1)") (class "Default")
      (node (ref "C13") (pin "1") (pinfunction "1_1") (pintype "passive"))
      (node (ref "U1") (pin "21") (pinfunction "DVDD_21") (pintype "bidirectional"))
      (node (ref "U1") (pin "22") (pinfunction "DVDD_22") (pintype "bidirectional"))
    )
    (net (code "26") (name "Net-(C21-Pad1)") (class "Default")
      (node (ref "C21") (pin "1") (pinfunction "1_1") (pintype "passive"))
      (node (ref "U2") (pin "CAP") (pinfunction "CAP_CAP") (pintype "bidirectional"))
    )
    (net (code "27") (name "Net-(C25-Pad2)") (class "Default")
      (node (ref "C25") (pin "2") (pinfunction "2_2") (pintype "passive"))
      (node (ref "U2") (pin "C1") (pinfunction "C1_C1") (pintype "bidirectional"))
    )
    (net (code "28") (name "Net-(D5-PadA)") (class "Default")
      (node (ref "D5") (pin "A") (pinfunction "A_A") (pintype "passive"))
      (node (ref "R10") (pin "2") (pinfunction "2_2") (pintype "passive"))
    )
    (net (code "29") (name "Net-(D6-PadA)") (class "Default")
      (node (ref "D6") (pin "A") (pinfunction "A_A") (pintype "passive"))
      (node (ref "R9") (pin "2") (pinfunction "2_2") (pintype "passive"))
    )
    (net (code "30") (name "Net-(JP1-1)") (class "Default")
      (node (ref "C1") (pin "1") (pinfunction "1_1") (pintype "passive"))
      (node (ref "JP1") (pin "DTR") (pinfunction "1_DTR") (pintype "passive"))
    )
    (net (code "31") (name "Net-(Q1-D)") (class "Default")
      (node (ref "D1") (pin "A") (pinfunction "A_A") (pintype "passive"))
      (node (ref "Q1") (pin "3D") (pinfunction "D_3D") (pintype "bidirectional"))
      (node (ref "U$2") (pin "V-") (pinfunction "V-_V-") (pintype "bidirectional"))
    )
    (net (code "32") (name "Net-(Q1-G)") (class "Default")
      (node (ref "C17") (pin "1") (pinfunction "1_1") (pintype "passive"))
      (node (ref "Q1") (pin "1G") (pinfunction "G_1G") (pintype "bidirectional"))
      (node (ref "R3") (pin "2") (pinfunction "2_2") (pintype "passive"))
      (node (ref "R7") (pin "2") (pinfunction "2_2") (pintype "passive"))
    )
    (net (code "33") (name "Net-(Q2-D)") (class "Default")
      (node (ref "D2") (pin "A") (pinfunction "A_A") (pintype "passive"))
      (node (ref "Q2") (pin "3D") (pinfunction "D_3D") (pintype "bidirectional"))
      (node (ref "U$4") (pin "V-") (pinfunction "V-_V-") (pintype "bidirectional"))
    )
    (net (code "34") (name "Net-(Q2-G)") (class "Default")
      (node (ref "C5") (pin "1") (pinfunction "1_1") (pintype "passive"))
      (node (ref "Q2") (pin "1G") (pinfunction "G_1G") (pintype "bidirectional"))
      (node (ref "R16") (pin "2") (pinfunction "2_2") (pintype "passive"))
      (node (ref "R17") (pin "2") (pinfunction "2_2") (pintype "passive"))
    )
    (net (code "35") (name "Net-(Q3-D)") (class "Default")
      (node (ref "D3") (pin "A") (pinfunction "A_A") (pintype "passive"))
      (node (ref "Q3") (pin "3D") (pinfunction "D_3D") (pintype "bidirectional"))
      (node (ref "U$5") (pin "V-") (pinfunction "V-_V-") (pintype "bidirectional"))
    )
    (net (code "36") (name "Net-(Q3-G)") (class "Default")
      (node (ref "C3") (pin "1") (pinfunction "1_1") (pintype "passive"))
      (node (ref "Q3") (pin "1G") (pinfunction "G_1G") (pintype "bidirectional"))
      (node (ref "R2") (pin "2") (pinfunction "2_2") (pintype "passive"))
      (node (ref "R4") (pin "2") (pinfunction "2_2") (pintype "passive"))
    )
    (net (code "37") (name "Net-(Q4-D)") (class "Default")
      (node (ref "D4") (pin "A") (pinfunction "A_A") (pintype "passive"))
      (node (ref "Q4") (pin "3D") (pinfunction "D_3D") (pintype "bidirectional"))
      (node (ref "U$6") (pin "V-") (pinfunction "V-_V-") (pintype "bidirectional"))
    )
    (net (code "38") (name "Net-(Q4-G)") (class "Default")
      (node (ref "C7") (pin "1") (pinfunction "1_1") (pintype "passive"))
      (node (ref "Q4") (pin "1G") (pinfunction "G_1G") (pintype "bidirectional"))
      (node (ref "R15") (pin "2") (pinfunction "2_2") (pintype "passive"))
      (node (ref "R6") (pin "2") (pinfunction "2_2") (pintype "passive"))
    )
    (net (code "39") (name "Net-(Q5-D)") (class "Default")
      (node (ref "D6") (pin "C") (pinfunction "C_C") (pintype "passive"))
      (node (ref "Q5") (pin "3D") (pinfunction "D_3D") (pintype "bidirectional"))
    )
    (net (code "40") (name "Net-(Q6-D)") (class "Default")
      (node (ref "D5") (pin "C") (pinfunction "C_C") (pintype "passive"))
      (node (ref "Q6") (pin "3D") (pinfunction "D_3D") (pintype "bidirectional"))
    )
    (net (code "41") (name "Net-(U$3-NC{slash}FB)") (class "Default")
      (node (ref "C16") (pin "1") (pinfunction "1_1") (pintype "passive"))
      (node (ref "U$3") (pin "4") (pinfunction "NC/FB_4") (pintype "passive"))
    )
    (net (code "42") (name "Net-(U1-AVDD)") (class "Default")
      (node (ref "C12") (pin "1") (pinfunction "1_1") (pintype "passive"))
      (node (ref "U1") (pin "60") (pinfunction "AVDD_60") (pintype "bidirectional"))
    )
    (net (code "43") (name "Net-(U1-XTAL1)") (class "Default")
      (node (ref "C27") (pin "1") (pinfunction "1_1") (pintype "passive"))
      (node (ref "U1") (pin "57") (pinfunction "XTAL1_57") (pintype "bidirectional"))
      (node (ref "Y1") (pin "3") (pinfunction "2_3") (pintype "passive"))
    )
    (net (code "44") (name "Net-(U1-XTAL2)") (class "Default")
      (node (ref "C26") (pin "1") (pinfunction "1_1") (pintype "passive"))
      (node (ref "U1") (pin "56") (pinfunction "XTAL2_56") (pintype "bidirectional"))
      (node (ref "Y1") (pin "1") (pinfunction "1_1") (pintype "passive"))
    )
    (net (code "45") (name "RESET") (class "Default")
      (node (ref "C1") (pin "2") (pinfunction "2_2") (pintype "passive"))
      (node (ref "J1") (pin "5") (pinfunction "5_5") (pintype "passive"))
      (node (ref "R1") (pin "2") (pinfunction "2_2") (pintype "passive"))
      (node (ref "SW1") (pin "1") (pinfunction "1_1") (pintype "passive"))
      (node (ref "SW1") (pin "2") (pinfunction "1_2") (pintype "passive"))
      (node (ref "U1") (pin "12") (pinfunction "RSTN_12") (pintype "bidirectional"))
    )
    (net (code "46") (name "unconnected-(J1-Pad2)") (class "Default")
      (node (ref "J1") (pin "2") (pinfunction "2_2") (pintype "passive"))
    )
    (net (code "47") (name "unconnected-(JP1-4-PadVCC)") (class "Default")
      (node (ref "JP1") (pin "VCC") (pinfunction "4_VCC") (pintype "passive"))
    )
    (net (code "48") (name "unconnected-(JP1-5-PadCTS)") (class "Default")
      (node (ref "JP1") (pin "CTS") (pinfunction "5_CTS") (pintype "passive"))
    )
    (net (code "49") (name "unconnected-(JP2-1-PadDTR)") (class "Default")
      (node (ref "JP2") (pin "DTR") (pinfunction "1_DTR") (pintype "passive"))
    )
    (net (code "50") (name "unconnected-(JP2-4-PadVCC)") (class "Default")
      (node (ref "JP2") (pin "VCC") (pinfunction "4_VCC") (pintype "passive"))
    )
    (net (code "51") (name "unconnected-(JP2-5-PadCTS)") (class "Default")
      (node (ref "JP2") (pin "CTS") (pinfunction "5_CTS") (pintype "passive"))
    )
    (net (code "52") (name "unconnected-(U1-AREF-Pad62)") (class "Default")
      (node (ref "U1") (pin "62") (pinfunction "AREF_62") (pintype "bidirectional"))
    )
    (net (code "53") (name "unconnected-(U1-PB0(SSN{slash}PCINT0)-Pad36)") (class "Default")
      (node (ref "U1") (pin "36") (pinfunction "PB0(SSN/PCINT0)_36") (pintype "bidirectional"))
    )
    (net (code "54") (name "unconnected-(U1-PB4(OC2A{slash}PCINT4)-Pad40)") (class "Default")
      (node (ref "U1") (pin "40") (pinfunction "PB4(OC2A/PCINT4)_40") (pintype "bidirectional"))
    )
    (net (code "55") (name "unconnected-(U1-PD4(ICP1)-Pad29)") (class "Default")
      (node (ref "U1") (pin "29") (pinfunction "PD4(ICP1)_29") (pintype "bidirectional"))
    )
    (net (code "56") (name "unconnected-(U1-PD5(XCK1)-Pad30)") (class "Default")
      (node (ref "U1") (pin "30") (pinfunction "PD5(XCK1)_30") (pintype "bidirectional"))
    )
    (net (code "57") (name "unconnected-(U1-PD6(T1)-Pad31)") (class "Default")
      (node (ref "U1") (pin "31") (pinfunction "PD6(T1)_31") (pintype "bidirectional"))
    )
    (net (code "58") (name "unconnected-(U1-PD7(T0)-Pad32)") (class "Default")
      (node (ref "U1") (pin "32") (pinfunction "PD7(T0)_32") (pintype "bidirectional"))
    )
    (net (code "59") (name "unconnected-(U1-PE2(XCK0{slash}AIN0)-Pad48)") (class "Default")
      (node (ref "U1") (pin "48") (pinfunction "PE2(XCK0/AIN0)_48") (pintype "bidirectional"))
    )
    (net (code "60") (name "unconnected-(U1-PE6(T3{slash}INT6)-Pad52)") (class "Default")
      (node (ref "U1") (pin "52") (pinfunction "PE6(T3/INT6)_52") (pintype "bidirectional"))
    )
    (net (code "61") (name "unconnected-(U1-PE7(ICP3{slash}INT7{slash}CLKO)-Pad53)") (class "Default")
      (node (ref "U1") (pin "53") (pinfunction "PE7(ICP3/INT7/CLKO)_53") (pintype "bidirectional"))
    )
    (net (code "62") (name "unconnected-(U1-PF0(ADC0)-Pad63)") (class "Default")
      (node (ref "U1") (pin "63") (pinfunction "PF0(ADC0)_63") (pintype "bidirectional"))
    )
    (net (code "63") (name "unconnected-(U1-PF1(ADC1)-Pad64)") (class "Default")
      (node (ref "U1") (pin "64") (pinfunction "PF1(ADC1)_64") (pintype "bidirectional"))
    )
    (net (code "64") (name "unconnected-(U1-PF2(ADC2{slash}DIG2)-Pad1)") (class "Default")
      (node (ref "U1") (pin "1") (pinfunction "PF2(ADC2/DIG2)_1") (pintype "bidirectional"))
    )
    (net (code "65") (name "unconnected-(U1-PF3(ADC3{slash}DIG4)-Pad2)") (class "Default")
      (node (ref "U1") (pin "2") (pinfunction "PF3(ADC3/DIG4)_2") (pintype "bidirectional"))
    )
    (net (code "66") (name "unconnected-(U1-PF4(ADC4{slash}TCK)-Pad3)") (class "Default")
      (node (ref "U1") (pin "3") (pinfunction "PF4(ADC4/TCK)_3") (pintype "bidirectional"))
    )
    (net (code "67") (name "unconnected-(U1-PF5(ADC5{slash}TMS)-Pad4)") (class "Default")
      (node (ref "U1") (pin "4") (pinfunction "PF5(ADC5/TMS)_4") (pintype "bidirectional"))
    )
    (net (code "68") (name "unconnected-(U1-PF6(ADC6{slash}TDO)-Pad5)") (class "Default")
      (node (ref "U1") (pin "5") (pinfunction "PF6(ADC6/TDO)_5") (pintype "bidirectional"))
    )
    (net (code "69") (name "unconnected-(U1-PF7(ADC7{slash}TDI)-Pad6)") (class "Default")
      (node (ref "U1") (pin "6") (pinfunction "PF7(ADC7/TDI)_6") (pintype "bidirectional"))
    )
    (net (code "70") (name "unconnected-(U1-PG0(DIG3)-Pad14)") (class "Default")
      (node (ref "U1") (pin "14") (pinfunction "PG0(DIG3)_14") (pintype "bidirectional"))
    )
    (net (code "71") (name "unconnected-(U1-PG1(DIG1)-Pad15)") (class "Default")
      (node (ref "U1") (pin "15") (pinfunction "PG1(DIG1)_15") (pintype "bidirectional"))
    )
    (net (code "72") (name "unconnected-(U1-PG2(AMR)-Pad16)") (class "Default")
      (node (ref "U1") (pin "16") (pinfunction "PG2(AMR)_16") (pintype "bidirectional"))
    )
    (net (code "73") (name "unconnected-(U1-PG5(OC0B)-Pad19)") (class "Default")
      (node (ref "U1") (pin "19") (pinfunction "PG5(OC0B)_19") (pintype "bidirectional"))
    )
    (net (code "74") (name "unconnected-(U1-RSTON-Pad13)") (class "Default")
      (node (ref "U1") (pin "13") (pinfunction "RSTON_13") (pintype "bidirectional"))
    )
    (net (code "75") (name "unconnected-(U2-PadDRDY_M)") (class "Default")
      (node (ref "U2") (pin "DRDY_M") (pinfunction "DRDY_M_DRDY_M") (pintype "bidirectional"))
    )
    (net (code "76") (name "unconnected-(U2-PadINT1_A{slash}G)") (class "Default")
      (node (ref "U2") (pin "INT1_A/G") (pinfunction "INT1_A/G_INT1_A/G") (pintype "bidirectional"))
    )
    (net (code "77") (name "unconnected-(U2-PadINT2_A{slash}G)") (class "Default")
      (node (ref "U2") (pin "INT2_A/G") (pinfunction "INT2_A/G_INT2_A/G") (pintype "bidirectional"))
    )
    (net (code "78") (name "unconnected-(U2-PadINT_M)") (class "Default")
      (node (ref "U2") (pin "INT_M") (pinfunction "INT_M_INT_M") (pintype "bidirectional"))
    )
  )
)
